# CH3.net
KiCad netlist of a schematic drawn in Altium Designer
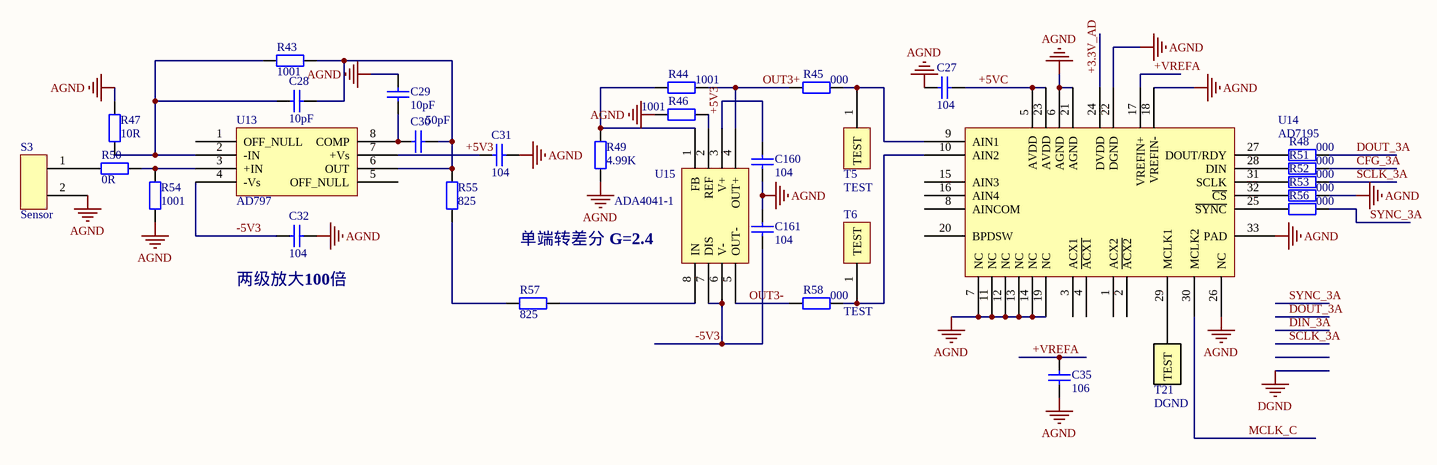
[diagram p0: CH3.SchDoc]

(export (version "E")
  (design (tool "Eeschema 10.0.6"))
  (components
    (comp (ref "C27")
      (value "104")
      (footprint "0805C")
      (description "Capacitor")
      (fields (field (name "PUBLISHER") "Altium Limited"))
      (libsource (lib "Miscellaneous Devices") (part "Cap"))
    )
    (comp (ref "C28")
      (value "10pF")
      (footprint "0603")
      (description "Capacitor")
      (fields (field (name "PUBLISHER") "Altium Limited"))
      (libsource (lib "Miscellaneous Devices") (part "Cap"))
    )
    (comp (ref "C29")
      (value "10pF")
      (footprint "0603")
      (description "Capacitor")
      (fields (field (name "PUBLISHER") "Altium Limited"))
      (libsource (lib "Miscellaneous Devices") (part "Cap"))
    )
    (comp (ref "C30")
      (value "50pF")
      (footprint "0603")
      (description "Capacitor")
      (fields (field (name "PUBLISHER") "Altium Limited"))
      (libsource (lib "Miscellaneous Devices") (part "Cap"))
    )
    (comp (ref "C31")
      (value "104")
      (footprint "0805C")
      (description "Capacitor")
      (fields (field (name "PUBLISHER") "Altium Limited"))
      (libsource (lib "Miscellaneous Devices") (part "Cap"))
    )
    (comp (ref "C32")
      (value "104")
      (footprint "0805C")
      (description "Capacitor")
      (fields (field (name "PUBLISHER") "Altium Limited"))
      (libsource (lib "Miscellaneous Devices") (part "Cap"))
    )
    (comp (ref "C35")
      (value "106")
      (footprint "0603")
      (description "Capacitor")
      (fields (field (name "PUBLISHER") "Altium Limited"))
      (libsource (lib "Miscellaneous Devices") (part "Cap"))
    )
    (comp (ref "C160")
      (value "104")
      (footprint "0805C")
      (description "Capacitor")
      (fields (field (name "PUBLISHER") "Altium Limited"))
      (libsource (lib "Miscellaneous Devices") (part "Cap"))
    )
    (comp (ref "C161")
      (value "104")
      (footprint "0805C")
      (description "Capacitor")
      (fields (field (name "PUBLISHER") "Altium Limited"))
      (libsource (lib "Miscellaneous Devices") (part "Cap"))
    )
    (comp (ref "R43")
      (value "1001")
      (footprint "0603")
      (description "Resistor")
      (fields (field (name "PUBLISHER") "Altium Limited"))
      (libsource (lib "Miscellaneous Devices") (part "Res2"))
    )
    (comp (ref "R44")
      (value "1001")
      (footprint "0603")
      (description "Resistor")
      (fields (field (name "PUBLISHER") "Altium Limited"))
      (libsource (lib "Miscellaneous Devices") (part "Res2"))
    )
    (comp (ref "R45")
      (value "000")
      (footprint "0603")
      (description "Resistor")
      (fields (field (name "PUBLISHER") "Altium Limited"))
      (libsource (lib "Miscellaneous Devices") (part "Res2"))
    )
    (comp (ref "R46")
      (value "1001")
      (footprint "0603")
      (description "Resistor")
      (fields (field (name "PUBLISHER") "Altium Limited"))
      (libsource (lib "Miscellaneous Devices") (part "Res2"))
    )
    (comp (ref "R47")
      (value "10R")
      (footprint "0603")
      (description "Resistor")
      (fields (field (name "PUBLISHER") "Altium Limited"))
      (libsource (lib "") (part "Res2_2"))
    )
    (comp (ref "R48")
      (value "000")
      (footprint "0603")
      (description "Resistor")
      (fields (field (name "PUBLISHER") "Altium Limited"))
      (libsource (lib "Miscellaneous Devices") (part "Res2"))
    )
    (comp (ref "R49")
      (value "4.99K")
      (footprint "0603")
      (description "Resistor")
      (fields (field (name "PUBLISHER") "Altium Limited"))
      (libsource (lib "") (part "Res2_1"))
    )
    (comp (ref "R50")
      (value "0R")
      (footprint "0603")
      (description "Resistor")
      (fields (field (name "PUBLISHER") "Altium Limited"))
      (libsource (lib "Miscellaneous Devices") (part "Res2"))
    )
    (comp (ref "R51")
      (value "000")
      (footprint "0603")
      (description "Resistor")
      (fields (field (name "PUBLISHER") "Altium Limited"))
      (libsource (lib "Miscellaneous Devices") (part "Res2"))
    )
    (comp (ref "R52")
      (value "000")
      (footprint "0603")
      (description "Resistor")
      (fields (field (name "PUBLISHER") "Altium Limited"))
      (libsource (lib "Miscellaneous Devices") (part "Res2"))
    )
    (comp (ref "R53")
      (value "000")
      (footprint "0603")
      (description "Resistor")
      (fields (field (name "PUBLISHER") "Altium Limited"))
      (libsource (lib "Miscellaneous Devices") (part "Res2"))
    )
    (comp (ref "R54")
      (value "1001")
      (footprint "0603")
      (description "Resistor")
      (fields (field (name "PUBLISHER") "Altium Limited"))
      (libsource (lib "") (part "Res2_1"))
    )
    (comp (ref "R55")
      (value "825")
      (footprint "0603")
      (description "Resistor")
      (fields (field (name "PUBLISHER") "Altium Limited"))
      (libsource (lib "") (part "Res2_1"))
    )
    (comp (ref "R56")
      (value "000")
      (footprint "0603")
      (description "Resistor")
      (fields (field (name "PUBLISHER") "Altium Limited"))
      (libsource (lib "Miscellaneous Devices") (part "Res2"))
    )
    (comp (ref "R57")
      (value "825")
      (footprint "0603")
      (description "Resistor")
      (fields (field (name "PUBLISHER") "Altium Limited"))
      (libsource (lib "Miscellaneous Devices") (part "Res2"))
    )
    (comp (ref "R58")
      (value "000")
      (footprint "0603")
      (description "Resistor")
      (fields (field (name "PUBLISHER") "Altium Limited"))
      (libsource (lib "Miscellaneous Devices") (part "Res2"))
    )
    (comp (ref "S3") (value "Sensor") (footprint "HDR1X2") (libsource (lib "Schlib1") (part "Sensor")))
    (comp (ref "T5") (value "TEST") (footprint "TEST") (libsource (lib "") (part "TEST_1")))
    (comp (ref "T6") (value "TEST") (footprint "TEST") (libsource (lib "Schlib1") (part "TEST")))
    (comp (ref "T21") (value "DGND") (footprint "TEST_2") (libsource (lib "USB30_Project") (part "TEST")))
    (comp (ref "U13") (value "AD797") (footprint "SO8") (libsource (lib "Schlib1") (part "AD797")))
    (comp (ref "U14") (value "AD7195") (footprint "VQFN32-1") (libsource (lib "Schlib1") (part "AD7195")))
    (comp (ref "U15") (value "ADA4041-1") (footprint "SO8") (libsource (lib "Schlib1") (part "ADA4041-1")))
  )
  (nets
    (net (code "1") (name "/+3.3V_AD") (class "Default")
      (node (ref "U14") (pin "24") (pinfunction "DVDD_24") (pintype "passive"))
    )
    (net (code "2") (name "/+5V3") (class "Default")
      (node (ref "C160") (pin "1") (pinfunction "1_1") (pintype "passive"))
      (node (ref "C31") (pin "2") (pinfunction "2_2") (pintype "passive"))
      (node (ref "U13") (pin "7") (pinfunction "+Vs_7") (pintype "passive"))
      (node (ref "U15") (pin "3") (pinfunction "V+_3") (pintype "passive"))
    )
    (net (code "3") (name "/+5VC") (class "Default")
      (node (ref "C27") (pin "2") (pinfunction "2_2") (pintype "passive"))
      (node (ref "U14") (pin "23") (pinfunction "AVDD_23") (pintype "passive"))
      (node (ref "U14") (pin "5") (pinfunction "AVDD_5") (pintype "passive"))
    )
    (net (code "4") (name "/+VREFA") (class "Default")
      (node (ref "C35") (pin "1") (pinfunction "1_1") (pintype "passive"))
      (node (ref "U14") (pin "17") (pinfunction "VREFIN+_17") (pintype "passive"))
    )
    (net (code "5") (name "/-5V3") (class "Default")
      (node (ref "C161") (pin "2") (pinfunction "2_2") (pintype "passive"))
      (node (ref "C32") (pin "2") (pinfunction "2_2") (pintype "passive"))
      (node (ref "U13") (pin "4") (pinfunction "-Vs_4") (pintype "passive"))
      (node (ref "U15") (pin "6") (pinfunction "V-_6") (pintype "passive"))
      (node (ref "U15") (pin "7") (pinfunction "DIS_7") (pintype "passive"))
    )
    (net (code "6") (name "/CFG_3A") (class "Default")
      (node (ref "R51") (pin "2") (pinfunction "2_2") (pintype "passive"))
    )
    (net (code "8") (name "/DOUT_3A") (class "Default")
      (node (ref "R48") (pin "2") (pinfunction "2_2") (pintype "passive"))
    )
    (net (code "9") (name "/MCLK_C") (class "Default")
      (node (ref "U14") (pin "30") (pinfunction "MCLK2_30") (pintype "passive"))
    )
    (net (code "10") (name "/OUT3+") (class "Default")
      (node (ref "R44") (pin "2") (pinfunction "2_2") (pintype "passive"))
      (node (ref "R45") (pin "1") (pinfunction "1_1") (pintype "passive"))
      (node (ref "U15") (pin "4") (pinfunction "OUT+_4") (pintype "passive"))
    )
    (net (code "11") (name "/OUT3-") (class "Default")
      (node (ref "R58") (pin "1") (pinfunction "1_1") (pintype "passive"))
      (node (ref "U15") (pin "5") (pinfunction "OUT-_5") (pintype "passive"))
    )
    (net (code "12") (name "/SCLK_3A") (class "Default")
      (node (ref "R52") (pin "2") (pinfunction "2_2") (pintype "passive"))
    )
    (net (code "13") (name "/SYNC_3A") (class "Default")
      (node (ref "R56") (pin "2") (pinfunction "2_2") (pintype "passive"))
    )
    (net (code "14") (name "AGND") (class "Default")
      (node (ref "C160") (pin "2") (pinfunction "2_2") (pintype "passive"))
      (node (ref "C161") (pin "1") (pinfunction "1_1") (pintype "passive"))
      (node (ref "C27") (pin "1") (pinfunction "1_1") (pintype "passive"))
      (node (ref "C29") (pin "2") (pinfunction "2_2") (pintype "passive"))
      (node (ref "C31") (pin "1") (pinfunction "1_1") (pintype "passive"))
      (node (ref "C32") (pin "1") (pinfunction "1_1") (pintype "passive"))
      (node (ref "C35") (pin "2") (pinfunction "2_2") (pintype "passive"))
      (node (ref "R46") (pin "1") (pinfunction "1_1") (pintype "passive"))
      (node (ref "R47") (pin "1") (pinfunction "1_1") (pintype "passive"))
      (node (ref "R49") (pin "1") (pinfunction "1_1") (pintype "passive"))
      (node (ref "R53") (pin "2") (pinfunction "2_2") (pintype "passive"))
      (node (ref "R54") (pin "1") (pinfunction "1_1") (pintype "passive"))
      (node (ref "S3") (pin "2") (pinfunction "2_2") (pintype "passive"))
      (node (ref "U14") (pin "11") (pinfunction "NC_11") (pintype "passive"))
      (node (ref "U14") (pin "12") (pinfunction "NC_12") (pintype "passive"))
      (node (ref "U14") (pin "13") (pinfunction "NC_13") (pintype "passive"))
      (node (ref "U14") (pin "14") (pinfunction "NC_14") (pintype "passive"))
      (node (ref "U14") (pin "18") (pinfunction "VREFIN-_18") (pintype "passive"))
      (node (ref "U14") (pin "19") (pinfunction "NC_19") (pintype "passive"))
      (node (ref "U14") (pin "21") (pinfunction "AGND_21") (pintype "passive"))
      (node (ref "U14") (pin "22") (pinfunction "DGND_22") (pintype "passive"))
      (node (ref "U14") (pin "26") (pinfunction "NC_26") (pintype "passive"))
      (node (ref "U14") (pin "33") (pinfunction "PAD_33") (pintype "passive"))
      (node (ref "U14") (pin "6") (pinfunction "AGND_6") (pintype "passive"))
      (node (ref "U14") (pin "7") (pinfunction "NC_7") (pintype "passive"))
    )
    (net (code "16") (name "Net-(R50-Pad1)") (class "Default")
      (node (ref "R50") (pin "1") (pinfunction "1_1") (pintype "passive"))
      (node (ref "S3") (pin "1") (pinfunction "1_1") (pintype "passive"))
    )
    (net (code "17") (name "Net-(R55-Pad1)") (class "Default")
      (node (ref "R55") (pin "1") (pinfunction "1_1") (pintype "passive"))
      (node (ref "R57") (pin "1") (pinfunction "1_1") (pintype "passive"))
    )
    (net (code "18") (name "Net-(T5-TEST)") (class "Default")
      (node (ref "R45") (pin "2") (pinfunction "2_2") (pintype "passive"))
      (node (ref "T5") (pin "1") (pinfunction "TEST_1") (pintype "passive"))
      (node (ref "U14") (pin "9") (pinfunction "AIN1_9") (pintype "passive"))
    )
    (net (code "19") (name "Net-(T6-TEST)") (class "Default")
      (node (ref "R58") (pin "2") (pinfunction "2_2") (pintype "passive"))
      (node (ref "T6") (pin "1") (pinfunction "TEST_1") (pintype "passive"))
      (node (ref "U14") (pin "10") (pinfunction "AIN2_10") (pintype "passive"))
    )
    (net (code "20") (name "Net-(T21-TEST)") (class "Default")
      (node (ref "T21") (pin "1") (pinfunction "TEST_1") (pintype "passive"))
      (node (ref "U14") (pin "29") (pinfunction "MCLK1_29") (pintype "passive"))
    )
    (net (code "21") (name "Net-(U13-+IN)") (class "Default")
      (node (ref "R50") (pin "2") (pinfunction "2_2") (pintype "passive"))
      (node (ref "R54") (pin "2") (pinfunction "2_2") (pintype "passive"))
      (node (ref "U13") (pin "3") (pinfunction "+IN_3") (pintype "passive"))
    )
    (net (code "22") (name "Net-(U13--IN)") (class "Default")
      (node (ref "C28") (pin "2") (pinfunction "2_2") (pintype "passive"))
      (node (ref "R43") (pin "1") (pinfunction "1_1") (pintype "passive"))
      (node (ref "R47") (pin "2") (pinfunction "2_2") (pintype "passive"))
      (node (ref "U13") (pin "2") (pinfunction "-IN_2") (pintype "passive"))
    )
    (net (code "23") (name "Net-(U13-COMP)") (class "Default")
      (node (ref "C29") (pin "1") (pinfunction "1_1") (pintype "passive"))
      (node (ref "C30") (pin "2") (pinfunction "2_2") (pintype "passive"))
      (node (ref "U13") (pin "8") (pinfunction "COMP_8") (pintype "passive"))
    )
    (net (code "24") (name "Net-(U13-OUT)") (class "Default")
      (node (ref "C28") (pin "1") (pinfunction "1_1") (pintype "passive"))
      (node (ref "C30") (pin "1") (pinfunction "1_1") (pintype "passive"))
      (node (ref "R43") (pin "2") (pinfunction "2_2") (pintype "passive"))
      (node (ref "R55") (pin "2") (pinfunction "2_2") (pintype "passive"))
      (node (ref "U13") (pin "6") (pinfunction "OUT_6") (pintype "passive"))
    )
    (net (code "25") (name "Net-(U14-DIN)") (class "Default")
      (node (ref "R51") (pin "1") (pinfunction "1_1") (pintype "passive"))
      (node (ref "U14") (pin "28") (pinfunction "DIN_28") (pintype "passive"))
    )
    (net (code "26") (name "Net-(U14-DOUT{slash}RDY)") (class "Default")
      (node (ref "R48") (pin "1") (pinfunction "1_1") (pintype "passive"))
      (node (ref "U14") (pin "27") (pinfunction "DOUT/RDY_27") (pintype "passive"))
    )
    (net (code "27") (name "Net-(U14-SCLK)") (class "Default")
      (node (ref "R52") (pin "1") (pinfunction "1_1") (pintype "passive"))
      (node (ref "U14") (pin "31") (pinfunction "SCLK_31") (pintype "passive"))
    )
    (net (code "28") (name "Net-(U14-~{CS})") (class "Default")
      (node (ref "R53") (pin "1") (pinfunction "1_1") (pintype "passive"))
      (node (ref "U14") (pin "32") (pinfunction "~{CS}_32") (pintype "passive"))
    )
    (net (code "29") (name "Net-(U14-~{SYNC})") (class "Default")
      (node (ref "R56") (pin "1") (pinfunction "1_1") (pintype "passive"))
      (node (ref "U14") (pin "25") (pinfunction "~{SYNC}_25") (pintype "passive"))
    )
    (net (code "30") (name "Net-(U15-FB)") (class "Default")
      (node (ref "R44") (pin "1") (pinfunction "1_1") (pintype "passive"))
      (node (ref "R49") (pin "2") (pinfunction "2_2") (pintype "passive"))
      (node (ref "U15") (pin "1") (pinfunction "FB_1") (pintype "passive"))
    )
    (net (code "31") (name "Net-(U15-IN)") (class "Default")
      (node (ref "R57") (pin "2") (pinfunction "2_2") (pintype "passive"))
      (node (ref "U15") (pin "8") (pinfunction "IN_8") (pintype "passive"))
    )
    (net (code "32") (name "Net-(U15-REF)") (class "Default")
      (node (ref "R46") (pin "2") (pinfunction "2_2") (pintype "passive"))
      (node (ref "U15") (pin "2") (pinfunction "REF_2") (pintype "passive"))
    )
    (net (code "33") (name "unconnected-(U13-OFF_NULL-Pad1)") (class "Default")
      (node (ref "U13") (pin "1") (pinfunction "OFF_NULL_1") (pintype "passive"))
    )
    (net (code "34") (name "unconnected-(U13-OFF_NULL-Pad5)") (class "Default")
      (node (ref "U13") (pin "5") (pinfunction "OFF_NULL_5") (pintype "passive"))
    )
    (net (code "35") (name "unconnected-(U14-ACX1-Pad3)") (class "Default")
      (node (ref "U14") (pin "3") (pinfunction "ACX1_3") (pintype "passive"))
    )
    (net (code "36") (name "unconnected-(U14-ACX2-Pad1)") (class "Default")
      (node (ref "U14") (pin "1") (pinfunction "ACX2_1") (pintype "passive"))
    )
    (net (code "37") (name "unconnected-(U14-AIN3-Pad15)") (class "Default")
      (node (ref "U14") (pin "15") (pinfunction "AIN3_15") (pintype "passive"))
    )
    (net (code "38") (name "unconnected-(U14-AIN4-Pad16)") (class "Default")
      (node (ref "U14") (pin "16") (pinfunction "AIN4_16") (pintype "passive"))
    )
    (net (code "39") (name "unconnected-(U14-AINCOM-Pad8)") (class "Default")
      (node (ref "U14") (pin "8") (pinfunction "AINCOM_8") (pintype "passive"))
    )
    (net (code "40") (name "unconnected-(U14-BPDSW-Pad20)") (class "Default")
      (node (ref "U14") (pin "20") (pinfunction "BPDSW_20") (pintype "passive"))
    )
    (net (code "41") (name "unconnected-(U14-~{ACX1}-Pad4)") (class "Default")
      (node (ref "U14") (pin "4") (pinfunction "~{ACX1}_4") (pintype "passive"))
    )
    (net (code "42") (name "unconnected-(U14-~{ACX2}-Pad2)") (class "Default")
      (node (ref "U14") (pin "2") (pinfunction "~{ACX2}_2") (pintype "passive"))
    )
  )
)
